# SCH_ZX_WiFi_2022-06-30.net
KiCad netlist of a schematic drawn in EasyEDA
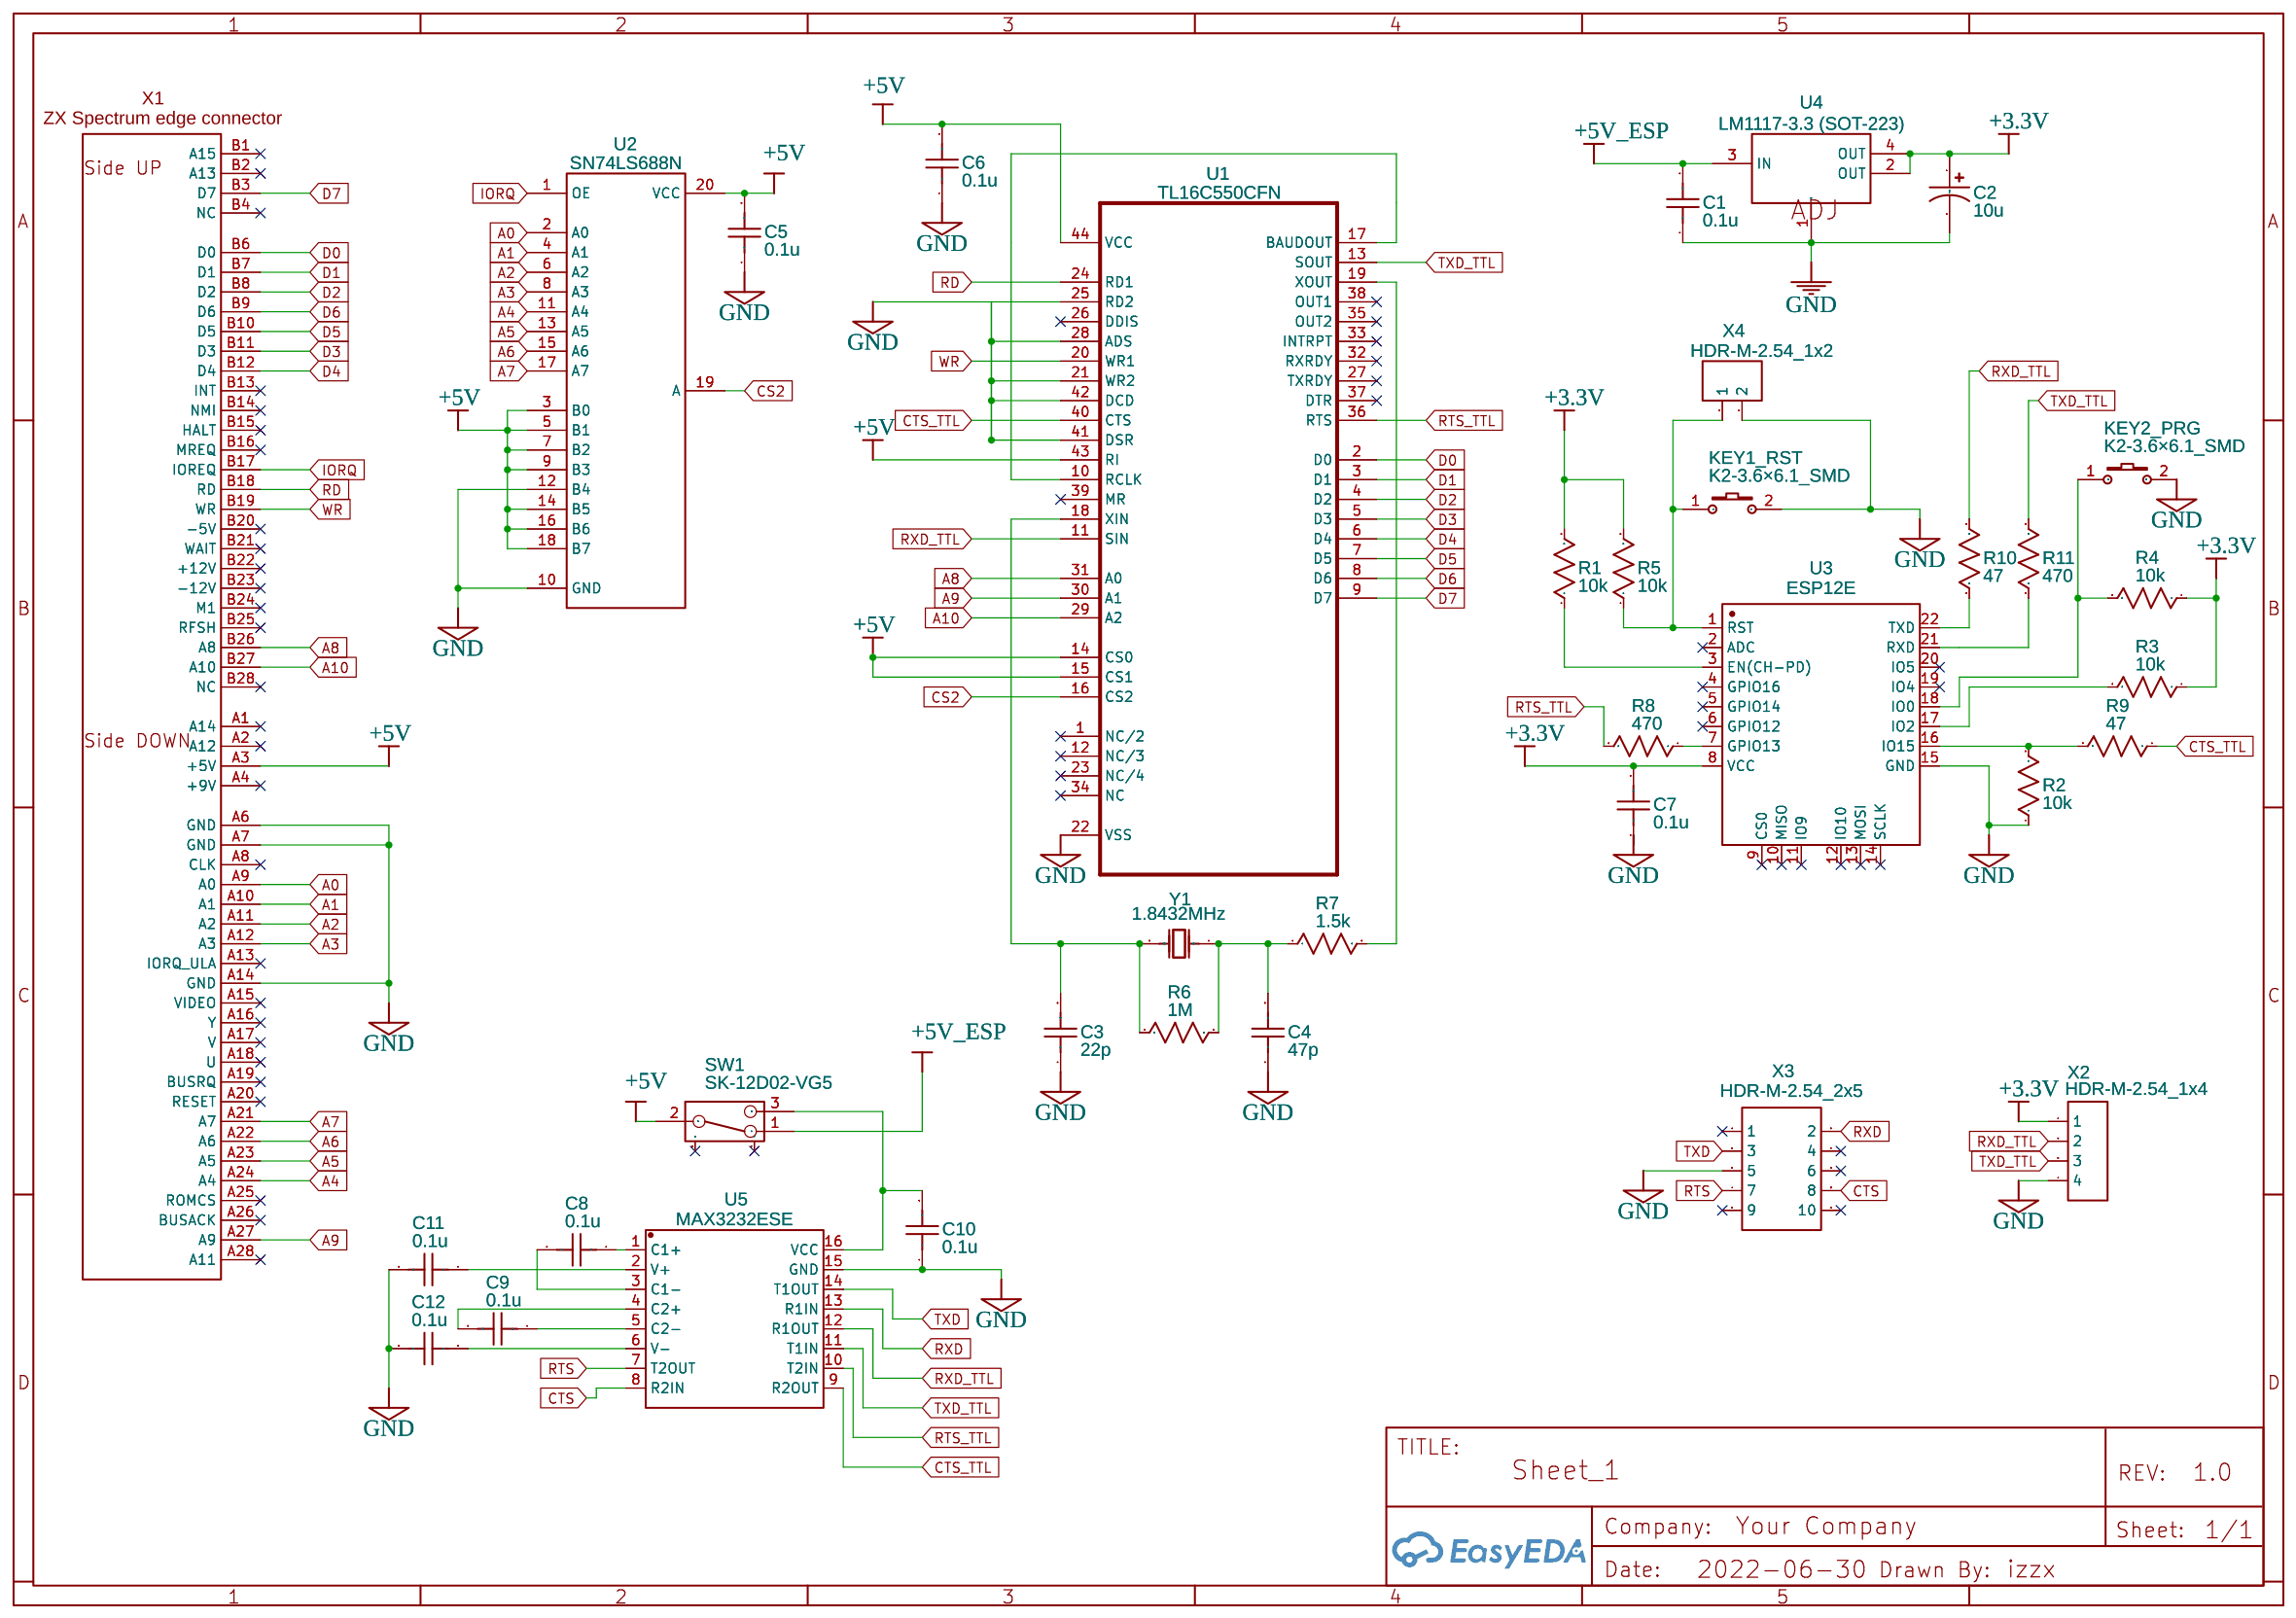
[diagram p0: schematic sheet]

(export (version "E")
  (design (tool "Eeschema 10.0.6"))
  (components
    (comp (ref "C1") (value "0.1u") (libsource (lib "") (part "C_0805_US")))
    (comp (ref "C2") (value "10u") (libsource (lib "") (part "C_Tan_SMD_A_US")))
    (comp (ref "C3") (value "22p") (libsource (lib "") (part "C_0805_US")))
    (comp (ref "C4") (value "47p") (libsource (lib "") (part "C_0805_US")))
    (comp (ref "C5") (value "0.1u") (libsource (lib "") (part "C_0805_US")))
    (comp (ref "C6") (value "0.1u") (libsource (lib "") (part "C_0805_US")))
    (comp (ref "C7") (value "0.1u") (libsource (lib "") (part "C_0805_US")))
    (comp (ref "C8") (value "0.1u") (libsource (lib "") (part "C_0805_US_1")))
    (comp (ref "C9") (value "0.1u") (libsource (lib "") (part "C_0805_US_1")))
    (comp (ref "C10") (value "0.1u") (libsource (lib "") (part "C_0805_US")))
    (comp (ref "C11") (value "0.1u") (libsource (lib "") (part "C_0805_US_1")))
    (comp (ref "C12") (value "0.1u") (libsource (lib "") (part "C_0805_US_1")))
    (comp (ref "KEY1_RST")
      (value "K2-3.6×6.1_SMD")
      (fields
        (field (name "BOM_Manufacturer Part") "K2-1107ST-A4SW-06")
        (field (name "BOM_Supplier Part") "C118141")
      )
      (libsource (lib "") (part "K2-3.6×6.1_SMD"))
    )
    (comp (ref "KEY2_PRG")
      (value "K2-3.6×6.1_SMD")
      (fields
        (field (name "BOM_Manufacturer Part") "K2-1107ST-A4SW-06")
        (field (name "BOM_Supplier Part") "C118141")
      )
      (libsource (lib "") (part "K2-3.6×6.1_SMD_1"))
    )
    (comp (ref "R1") (value "10k") (libsource (lib "") (part "R_0805_US")))
    (comp (ref "R2") (value "10k") (libsource (lib "") (part "R_0805_US")))
    (comp (ref "R3") (value "10k") (libsource (lib "") (part "R_0805_US_1")))
    (comp (ref "R4") (value "10k") (libsource (lib "") (part "R_0805_US_1")))
    (comp (ref "R5") (value "10k") (libsource (lib "") (part "R_0805_US")))
    (comp (ref "R6") (value "1M") (libsource (lib "") (part "R_0805_US_2")))
    (comp (ref "R7") (value "1.5k") (libsource (lib "") (part "R_0805_US_2")))
    (comp (ref "R8") (value "470") (libsource (lib "") (part "R_0805_US_1")))
    (comp (ref "R9") (value "47") (libsource (lib "") (part "R_0805_US_1")))
    (comp (ref "R10") (value "47") (libsource (lib "") (part "R_0805_US")))
    (comp (ref "R11") (value "470") (libsource (lib "") (part "R_0805_US")))
    (comp (ref "SW1")
      (value "SK-12D02-VG5")
      (fields (field (name "BOM_Supplier Part") "C136722"))
      (libsource (lib "") (part "SK-12D02-VG5"))
    )
    (comp (ref "U1") (value "TL16C550CFN") (libsource (lib "") (part "TL16C550CFN")))
    (comp (ref "U2") (value "SN74LS688N") (libsource (lib "") (part "SN74LS688N")))
    (comp (ref "U3") (value "ESP12E") (libsource (lib "") (part "ESP12E/F")))
    (comp (ref "U4")
      (value "LM1117-3.3 (SOT-223)")
      (fields
        (field (name "BOM_Manufacturer Part") "LM317G-AA3-R")
        (field (name "BOM_Supplier Part") "C19651")
      )
      (libsource (lib "") (part "LM317(SOT-223)"))
    )
    (comp (ref "U5")
      (value "MAX3232ESE")
      (fields (field (name "BOM_Supplier Part") "C2904738"))
      (libsource (lib "") (part "MAX3232ESE"))
    )
    (comp (ref "X1") (value "ZX SPECTRUM CONNECTOR") (libsource (lib "") (part "ZX SPECTRUM CONNECTOR")))
    (comp (ref "X2")
      (value "HDR-M-2.54_1x4")
      (fields (field (name "BOM_Supplier Part") "C124378"))
      (libsource (lib "") (part "HDR-M-2.54_1x4"))
    )
    (comp (ref "X3")
      (value "HDR-M-2.54_2x5")
      (fields (field (name "BOM_Supplier Part") "C178292"))
      (libsource (lib "") (part "HDR-M-2.54_2x5"))
    )
    (comp (ref "X4")
      (value "HDR-M-2.54_1x2")
      (fields (field (name "BOM_Supplier Part") "C124375"))
      (libsource (lib "") (part "HDR-M-2.54_1x2"))
    )
    (comp (ref "Y1")
      (value "1.8432MHz")
      (fields
        (field (name "BOM_Manufacturer Part") "X49UD3579MSD2SC")
        (field (name "BOM_Supplier Part") "C36564")
      )
      (libsource (lib "") (part "X49UD3579MSD2SC"))
    )
  )
  (nets
    (net (code "1") (name "+3.3V") (class "Default")
      (node (ref "C2") (pin "1") (pinfunction "1_1") (pintype "unspecified"))
      (node (ref "C7") (pin "2") (pinfunction "2_2") (pintype "unspecified"))
      (node (ref "R1") (pin "2") (pinfunction "2_2") (pintype "unspecified"))
      (node (ref "R3") (pin "1") (pinfunction "1_1") (pintype "unspecified"))
      (node (ref "R4") (pin "1") (pinfunction "1_1") (pintype "unspecified"))
      (node (ref "R5") (pin "2") (pinfunction "2_2") (pintype "unspecified"))
      (node (ref "U3") (pin "8") (pinfunction "VCC_8") (pintype "unspecified"))
      (node (ref "U4") (pin "2") (pinfunction "OUT_2") (pintype "passive"))
      (node (ref "U4") (pin "4") (pinfunction "OUT_4") (pintype "passive"))
      (node (ref "X2") (pin "1") (pinfunction "1_1") (pintype "unspecified"))
    )
    (net (code "2") (name "+5V") (class "Default")
      (node (ref "C5") (pin "2") (pinfunction "2_2") (pintype "unspecified"))
      (node (ref "C6") (pin "2") (pinfunction "2_2") (pintype "unspecified"))
      (node (ref "SW1") (pin "2") (pinfunction "2_2") (pintype "unspecified"))
      (node (ref "U1") (pin "14") (pinfunction "CS0_14") (pintype "input"))
      (node (ref "U1") (pin "15") (pinfunction "CS1_15") (pintype "input"))
      (node (ref "U1") (pin "43") (pinfunction "RI_43") (pintype "input"))
      (node (ref "U1") (pin "44") (pinfunction "VCC_44") (pintype "passive"))
      (node (ref "U2") (pin "14") (pinfunction "B5_14") (pintype "unspecified"))
      (node (ref "U2") (pin "16") (pinfunction "B6_16") (pintype "unspecified"))
      (node (ref "U2") (pin "18") (pinfunction "B7_18") (pintype "unspecified"))
      (node (ref "U2") (pin "20") (pinfunction "VCC_20") (pintype "passive"))
      (node (ref "U2") (pin "3") (pinfunction "B0_3") (pintype "unspecified"))
      (node (ref "U2") (pin "5") (pinfunction "B1_5") (pintype "unspecified"))
      (node (ref "U2") (pin "7") (pinfunction "B2_7") (pintype "unspecified"))
      (node (ref "U2") (pin "9") (pinfunction "B3_9") (pintype "unspecified"))
      (node (ref "X1") (pin "A3") (pinfunction "+5V_A3") (pintype "unspecified"))
    )
    (net (code "3") (name "+5V_ESP") (class "Default")
      (node (ref "C1") (pin "2") (pinfunction "2_2") (pintype "unspecified"))
      (node (ref "SW1") (pin "1") (pinfunction "1_1") (pintype "unspecified"))
      (node (ref "U4") (pin "3") (pinfunction "IN_3") (pintype "passive"))
    )
    (net (code "4") (name "A0") (class "Default")
      (node (ref "U2") (pin "2") (pinfunction "A0_2") (pintype "unspecified"))
      (node (ref "X1") (pin "A9") (pinfunction "A0_A9") (pintype "unspecified"))
    )
    (net (code "5") (name "A1") (class "Default")
      (node (ref "U2") (pin "4") (pinfunction "A1_4") (pintype "unspecified"))
      (node (ref "X1") (pin "A10") (pinfunction "A1_A10") (pintype "unspecified"))
    )
    (net (code "6") (name "A2") (class "Default")
      (node (ref "U2") (pin "6") (pinfunction "A2_6") (pintype "unspecified"))
      (node (ref "X1") (pin "A11") (pinfunction "A2_A11") (pintype "unspecified"))
    )
    (net (code "7") (name "A3") (class "Default")
      (node (ref "U2") (pin "8") (pinfunction "A3_8") (pintype "unspecified"))
      (node (ref "X1") (pin "A12") (pinfunction "A3_A12") (pintype "unspecified"))
    )
    (net (code "8") (name "A4") (class "Default")
      (node (ref "U2") (pin "11") (pinfunction "A4_11") (pintype "unspecified"))
      (node (ref "X1") (pin "A24") (pinfunction "A4_A24") (pintype "unspecified"))
    )
    (net (code "9") (name "A5") (class "Default")
      (node (ref "U2") (pin "13") (pinfunction "A5_13") (pintype "unspecified"))
      (node (ref "X1") (pin "A23") (pinfunction "A5_A23") (pintype "unspecified"))
    )
    (net (code "10") (name "A6") (class "Default")
      (node (ref "U2") (pin "15") (pinfunction "A6_15") (pintype "unspecified"))
      (node (ref "X1") (pin "A22") (pinfunction "A6_A22") (pintype "unspecified"))
    )
    (net (code "11") (name "A7") (class "Default")
      (node (ref "U2") (pin "17") (pinfunction "A7_17") (pintype "unspecified"))
      (node (ref "X1") (pin "A21") (pinfunction "A7_A21") (pintype "unspecified"))
    )
    (net (code "12") (name "A8") (class "Default")
      (node (ref "U1") (pin "31") (pinfunction "A0_31") (pintype "input"))
      (node (ref "X1") (pin "B26") (pinfunction "A8_B26") (pintype "unspecified"))
    )
    (net (code "13") (name "A9") (class "Default")
      (node (ref "U1") (pin "30") (pinfunction "A1_30") (pintype "input"))
      (node (ref "X1") (pin "A27") (pinfunction "A9_A27") (pintype "unspecified"))
    )
    (net (code "14") (name "A10") (class "Default")
      (node (ref "U1") (pin "29") (pinfunction "A2_29") (pintype "input"))
      (node (ref "X1") (pin "B27") (pinfunction "A10_B27") (pintype "unspecified"))
    )
    (net (code "15") (name "CS2") (class "Default")
      (node (ref "U1") (pin "16") (pinfunction "CS2_16") (pintype "input"))
      (node (ref "U2") (pin "19") (pinfunction "A_19") (pintype "output"))
    )
    (net (code "16") (name "CTS") (class "Default")
      (node (ref "U5") (pin "8") (pinfunction "R2IN_8") (pintype "unspecified"))
      (node (ref "X3") (pin "8") (pinfunction "8_8") (pintype "unspecified"))
    )
    (net (code "17") (name "CTS_TTL") (class "Default")
      (node (ref "R9") (pin "1") (pinfunction "1_1") (pintype "unspecified"))
      (node (ref "U1") (pin "40") (pinfunction "CTS_40") (pintype "input"))
      (node (ref "U5") (pin "9") (pinfunction "R2OUT_9") (pintype "unspecified"))
    )
    (net (code "18") (name "D0") (class "Default")
      (node (ref "U1") (pin "2") (pinfunction "D0_2") (pintype "unspecified"))
      (node (ref "X1") (pin "B6") (pinfunction "D0_B6") (pintype "bidirectional"))
    )
    (net (code "19") (name "D1") (class "Default")
      (node (ref "U1") (pin "3") (pinfunction "D1_3") (pintype "unspecified"))
      (node (ref "X1") (pin "B7") (pinfunction "D1_B7") (pintype "bidirectional"))
    )
    (net (code "20") (name "D2") (class "Default")
      (node (ref "U1") (pin "4") (pinfunction "D2_4") (pintype "unspecified"))
      (node (ref "X1") (pin "B8") (pinfunction "D2_B8") (pintype "bidirectional"))
    )
    (net (code "21") (name "D3") (class "Default")
      (node (ref "U1") (pin "5") (pinfunction "D3_5") (pintype "unspecified"))
      (node (ref "X1") (pin "B11") (pinfunction "D3_B11") (pintype "unspecified"))
    )
    (net (code "22") (name "D4") (class "Default")
      (node (ref "U1") (pin "6") (pinfunction "D4_6") (pintype "unspecified"))
      (node (ref "X1") (pin "B12") (pinfunction "D4_B12") (pintype "unspecified"))
    )
    (net (code "23") (name "D5") (class "Default")
      (node (ref "U1") (pin "7") (pinfunction "D5_7") (pintype "unspecified"))
      (node (ref "X1") (pin "B10") (pinfunction "D5_B10") (pintype "bidirectional"))
    )
    (net (code "24") (name "D6") (class "Default")
      (node (ref "U1") (pin "8") (pinfunction "D6_8") (pintype "unspecified"))
      (node (ref "X1") (pin "B9") (pinfunction "D6_B9") (pintype "unspecified"))
    )
    (net (code "25") (name "D7") (class "Default")
      (node (ref "U1") (pin "9") (pinfunction "D7_9") (pintype "unspecified"))
      (node (ref "X1") (pin "B3") (pinfunction "D7_B3") (pintype "bidirectional"))
    )
    (net (code "26") (name "GND") (class "Default")
      (node (ref "C1") (pin "1") (pinfunction "1_1") (pintype "unspecified"))
      (node (ref "C10") (pin "1") (pinfunction "1_1") (pintype "unspecified"))
      (node (ref "C11") (pin "2") (pinfunction "2_2") (pintype "unspecified"))
      (node (ref "C12") (pin "2") (pinfunction "2_2") (pintype "unspecified"))
      (node (ref "C2") (pin "2") (pinfunction "2_2") (pintype "unspecified"))
      (node (ref "C3") (pin "1") (pinfunction "1_1") (pintype "unspecified"))
      (node (ref "C4") (pin "1") (pinfunction "1_1") (pintype "unspecified"))
      (node (ref "C5") (pin "1") (pinfunction "1_1") (pintype "unspecified"))
      (node (ref "C6") (pin "1") (pinfunction "1_1") (pintype "unspecified"))
      (node (ref "C7") (pin "1") (pinfunction "1_1") (pintype "unspecified"))
      (node (ref "KEY1_RST") (pin "2") (pinfunction "2_2") (pintype "unspecified"))
      (node (ref "KEY2_PRG") (pin "2") (pinfunction "2_2") (pintype "unspecified"))
      (node (ref "R2") (pin "1") (pinfunction "1_1") (pintype "unspecified"))
      (node (ref "U1") (pin "21") (pinfunction "WR2_21") (pintype "input"))
      (node (ref "U1") (pin "22") (pinfunction "VSS_22") (pintype "passive"))
      (node (ref "U1") (pin "25") (pinfunction "RD2_25") (pintype "input"))
      (node (ref "U1") (pin "28") (pinfunction "ADS_28") (pintype "input"))
      (node (ref "U1") (pin "41") (pinfunction "DSR_41") (pintype "input"))
      (node (ref "U1") (pin "42") (pinfunction "DCD_42") (pintype "input"))
      (node (ref "U2") (pin "10") (pinfunction "GND_10") (pintype "passive"))
      (node (ref "U2") (pin "12") (pinfunction "B4_12") (pintype "unspecified"))
      (node (ref "U3") (pin "15") (pinfunction "GND_15") (pintype "unspecified"))
      (node (ref "U4") (pin "1") (pinfunction "ADJ_1") (pintype "passive"))
      (node (ref "U5") (pin "15") (pinfunction "GND_15") (pintype "unspecified"))
      (node (ref "X1") (pin "A14") (pinfunction "GND_A14") (pintype "unspecified"))
      (node (ref "X1") (pin "A6") (pinfunction "GND_A6") (pintype "unspecified"))
      (node (ref "X1") (pin "A7") (pinfunction "GND_A7") (pintype "unspecified"))
      (node (ref "X2") (pin "4") (pinfunction "4_4") (pintype "unspecified"))
      (node (ref "X3") (pin "5") (pinfunction "5_5") (pintype "unspecified"))
      (node (ref "X4") (pin "2") (pinfunction "2_2") (pintype "unspecified"))
    )
    (net (code "27") (name "IORQ") (class "Default")
      (node (ref "U2") (pin "1") (pinfunction "OE_1") (pintype "unspecified"))
      (node (ref "X1") (pin "B17") (pinfunction "IOREQ_B17") (pintype "unspecified"))
    )
    (net (code "28") (name "Net-(U1-BAUDOUT)") (class "Default")
      (node (ref "U1") (pin "10") (pinfunction "RCLK_10") (pintype "input"))
      (node (ref "U1") (pin "17") (pinfunction "BAUDOUT_17") (pintype "output"))
    )
    (net (code "29") (name "Net-(U1-XIN)") (class "Default")
      (node (ref "C3") (pin "2") (pinfunction "2_2") (pintype "unspecified"))
      (node (ref "R6") (pin "1") (pinfunction "1_1") (pintype "unspecified"))
      (node (ref "U1") (pin "18") (pinfunction "XIN_18") (pintype "input"))
      (node (ref "Y1") (pin "2") (pinfunction "OSC2_2") (pintype "input"))
    )
    (net (code "30") (name "Net-(U1-XOUT)") (class "Default")
      (node (ref "R7") (pin "2") (pinfunction "2_2") (pintype "unspecified"))
      (node (ref "U1") (pin "19") (pinfunction "XOUT_19") (pintype "output"))
    )
    (net (code "31") (name "Net-(U3-EN(CH-PD))") (class "Default")
      (node (ref "R1") (pin "1") (pinfunction "1_1") (pintype "unspecified"))
      (node (ref "U3") (pin "3") (pinfunction "EN(CH-PD)_3") (pintype "unspecified"))
    )
    (net (code "32") (name "Net-(U3-GPIO13)") (class "Default")
      (node (ref "R8") (pin "1") (pinfunction "1_1") (pintype "unspecified"))
      (node (ref "U3") (pin "7") (pinfunction "GPIO13_7") (pintype "unspecified"))
    )
    (net (code "33") (name "Net-(U3-IO0)") (class "Default")
      (node (ref "KEY2_PRG") (pin "1") (pinfunction "1_1") (pintype "unspecified"))
      (node (ref "R4") (pin "2") (pinfunction "2_2") (pintype "unspecified"))
      (node (ref "U3") (pin "18") (pinfunction "IO0_18") (pintype "unspecified"))
    )
    (net (code "34") (name "Net-(U3-IO2)") (class "Default")
      (node (ref "R3") (pin "2") (pinfunction "2_2") (pintype "unspecified"))
      (node (ref "U3") (pin "17") (pinfunction "IO2_17") (pintype "unspecified"))
    )
    (net (code "35") (name "Net-(U3-IO15)") (class "Default")
      (node (ref "R2") (pin "2") (pinfunction "2_2") (pintype "unspecified"))
      (node (ref "R9") (pin "2") (pinfunction "2_2") (pintype "unspecified"))
      (node (ref "U3") (pin "16") (pinfunction "IO15_16") (pintype "unspecified"))
    )
    (net (code "36") (name "Net-(U3-RST)") (class "Default")
      (node (ref "KEY1_RST") (pin "1") (pinfunction "1_1") (pintype "unspecified"))
      (node (ref "R5") (pin "1") (pinfunction "1_1") (pintype "unspecified"))
      (node (ref "U3") (pin "1") (pinfunction "RST_1") (pintype "unspecified"))
      (node (ref "X4") (pin "1") (pinfunction "1_1") (pintype "unspecified"))
    )
    (net (code "37") (name "Net-(U3-RXD)") (class "Default")
      (node (ref "R11") (pin "1") (pinfunction "1_1") (pintype "unspecified"))
      (node (ref "U3") (pin "21") (pinfunction "RXD_21") (pintype "unspecified"))
    )
    (net (code "38") (name "Net-(U3-TXD)") (class "Default")
      (node (ref "R10") (pin "1") (pinfunction "1_1") (pintype "unspecified"))
      (node (ref "U3") (pin "22") (pinfunction "TXD_22") (pintype "unspecified"))
    )
    (net (code "39") (name "Net-(U5-C1+)") (class "Default")
      (node (ref "C8") (pin "1") (pinfunction "1_1") (pintype "unspecified"))
      (node (ref "U5") (pin "1") (pinfunction "C1+_1") (pintype "unspecified"))
    )
    (net (code "40") (name "Net-(U5-C1-)") (class "Default")
      (node (ref "C8") (pin "2") (pinfunction "2_2") (pintype "unspecified"))
      (node (ref "U5") (pin "3") (pinfunction "C1-_3") (pintype "unspecified"))
    )
    (net (code "41") (name "Net-(U5-C2+)") (class "Default")
      (node (ref "C9") (pin "2") (pinfunction "2_2") (pintype "unspecified"))
      (node (ref "U5") (pin "4") (pinfunction "C2+_4") (pintype "unspecified"))
    )
    (net (code "42") (name "Net-(U5-C2-)") (class "Default")
      (node (ref "C9") (pin "1") (pinfunction "1_1") (pintype "unspecified"))
      (node (ref "U5") (pin "5") (pinfunction "C2-_5") (pintype "unspecified"))
    )
    (net (code "43") (name "Net-(U5-V+)") (class "Default")
      (node (ref "C11") (pin "1") (pinfunction "1_1") (pintype "unspecified"))
      (node (ref "U5") (pin "2") (pinfunction "V+_2") (pintype "unspecified"))
    )
    (net (code "44") (name "Net-(U5-V-)") (class "Default")
      (node (ref "C12") (pin "1") (pinfunction "1_1") (pintype "unspecified"))
      (node (ref "U5") (pin "6") (pinfunction "V-_6") (pintype "unspecified"))
    )
    (net (code "45") (name "Net-(U5-VCC)") (class "Default")
      (node (ref "C10") (pin "2") (pinfunction "2_2") (pintype "unspecified"))
      (node (ref "SW1") (pin "3") (pinfunction "3_3") (pintype "unspecified"))
      (node (ref "U5") (pin "16") (pinfunction "VCC_16") (pintype "unspecified"))
    )
    (net (code "46") (name "Net-(Y1-OSC1)") (class "Default")
      (node (ref "C4") (pin "2") (pinfunction "2_2") (pintype "unspecified"))
      (node (ref "R6") (pin "2") (pinfunction "2_2") (pintype "unspecified"))
      (node (ref "R7") (pin "1") (pinfunction "1_1") (pintype "unspecified"))
      (node (ref "Y1") (pin "1") (pinfunction "OSC1_1") (pintype "input"))
    )
    (net (code "47") (name "RD") (class "Default")
      (node (ref "U1") (pin "24") (pinfunction "RD1_24") (pintype "input"))
      (node (ref "X1") (pin "B18") (pinfunction "RD_B18") (pintype "unspecified"))
    )
    (net (code "48") (name "RTS") (class "Default")
      (node (ref "U5") (pin "7") (pinfunction "T2OUT_7") (pintype "unspecified"))
      (node (ref "X3") (pin "7") (pinfunction "7_7") (pintype "unspecified"))
    )
    (net (code "49") (name "RTS_TTL") (class "Default")
      (node (ref "R8") (pin "2") (pinfunction "2_2") (pintype "unspecified"))
      (node (ref "U1") (pin "36") (pinfunction "RTS_36") (pintype "output"))
      (node (ref "U5") (pin "10") (pinfunction "T2IN_10") (pintype "unspecified"))
    )
    (net (code "50") (name "RXD") (class "Default")
      (node (ref "U5") (pin "13") (pinfunction "R1IN_13") (pintype "unspecified"))
      (node (ref "X3") (pin "2") (pinfunction "2_2") (pintype "unspecified"))
    )
    (net (code "51") (name "RXD_TTL") (class "Default")
      (node (ref "R10") (pin "2") (pinfunction "2_2") (pintype "unspecified"))
      (node (ref "U1") (pin "11") (pinfunction "SIN_11") (pintype "input"))
      (node (ref "U5") (pin "12") (pinfunction "R1OUT_12") (pintype "unspecified"))
      (node (ref "X2") (pin "2") (pinfunction "2_2") (pintype "unspecified"))
    )
    (net (code "52") (name "TXD") (class "Default")
      (node (ref "U5") (pin "14") (pinfunction "T1OUT_14") (pintype "unspecified"))
      (node (ref "X3") (pin "3") (pinfunction "3_3") (pintype "unspecified"))
    )
    (net (code "53") (name "TXD_TTL") (class "Default")
      (node (ref "R11") (pin "2") (pinfunction "2_2") (pintype "unspecified"))
      (node (ref "U1") (pin "13") (pinfunction "SOUT_13") (pintype "output"))
      (node (ref "U5") (pin "11") (pinfunction "T1IN_11") (pintype "unspecified"))
      (node (ref "X2") (pin "3") (pinfunction "3_3") (pintype "unspecified"))
    )
    (net (code "54") (name "WR") (class "Default")
      (node (ref "U1") (pin "20") (pinfunction "WR1_20") (pintype "input"))
      (node (ref "X1") (pin "B19") (pinfunction "WR_B19") (pintype "unspecified"))
    )
    (net (code "55") (name "unconnected-(SW1-Pad4)") (class "Default")
      (node (ref "SW1") (pin "4") (pinfunction "4_4") (pintype "unspecified+no_connect"))
    )
    (net (code "56") (name "unconnected-(SW1-Pad5)") (class "Default")
      (node (ref "SW1") (pin "5") (pinfunction "5_5") (pintype "unspecified+no_connect"))
    )
    (net (code "57") (name "unconnected-(U1-DDIS-Pad26)") (class "Default")
      (node (ref "U1") (pin "26") (pinfunction "DDIS_26") (pintype "input+no_connect"))
    )
    (net (code "58") (name "unconnected-(U1-DTR-Pad37)") (class "Default")
      (node (ref "U1") (pin "37") (pinfunction "DTR_37") (pintype "output+no_connect"))
    )
    (net (code "59") (name "unconnected-(U1-INTRPT-Pad33)") (class "Default")
      (node (ref "U1") (pin "33") (pinfunction "INTRPT_33") (pintype "output+no_connect"))
    )
    (net (code "60") (name "unconnected-(U1-MR-Pad39)") (class "Default")
      (node (ref "U1") (pin "39") (pinfunction "MR_39") (pintype "input+no_connect"))
    )
    (net (code "61") (name "unconnected-(U1-NC-Pad34)") (class "Default")
      (node (ref "U1") (pin "34") (pinfunction "NC_34") (pintype "unspecified+no_connect"))
    )
    (net (code "62") (name "unconnected-(U1-NC{slash}2-Pad1)") (class "Default")
      (node (ref "U1") (pin "1") (pinfunction "NC/2_1") (pintype "unspecified+no_connect"))
    )
    (net (code "63") (name "unconnected-(U1-NC{slash}3-Pad12)") (class "Default")
      (node (ref "U1") (pin "12") (pinfunction "NC/3_12") (pintype "unspecified+no_connect"))
    )
    (net (code "64") (name "unconnected-(U1-NC{slash}4-Pad23)") (class "Default")
      (node (ref "U1") (pin "23") (pinfunction "NC/4_23") (pintype "unspecified+no_connect"))
    )
    (net (code "65") (name "unconnected-(U1-OUT1-Pad38)") (class "Default")
      (node (ref "U1") (pin "38") (pinfunction "OUT1_38") (pintype "output+no_connect"))
    )
    (net (code "66") (name "unconnected-(U1-OUT2-Pad35)") (class "Default")
      (node (ref "U1") (pin "35") (pinfunction "OUT2_35") (pintype "output+no_connect"))
    )
    (net (code "67") (name "unconnected-(U1-RXRDY-Pad32)") (class "Default")
      (node (ref "U1") (pin "32") (pinfunction "RXRDY_32") (pintype "output+no_connect"))
    )
    (net (code "68") (name "unconnected-(U1-TXRDY-Pad27)") (class "Default")
      (node (ref "U1") (pin "27") (pinfunction "TXRDY_27") (pintype "output+no_connect"))
    )
    (net (code "69") (name "unconnected-(U3-ADC-Pad2)") (class "Default")
      (node (ref "U3") (pin "2") (pinfunction "ADC_2") (pintype "unspecified+no_connect"))
    )
    (net (code "70") (name "unconnected-(U3-CS0-Pad9)") (class "Default")
      (node (ref "U3") (pin "9") (pinfunction "CS0_9") (pintype "unspecified+no_connect"))
    )
    (net (code "71") (name "unconnected-(U3-GPIO12-Pad6)") (class "Default")
      (node (ref "U3") (pin "6") (pinfunction "GPIO12_6") (pintype "unspecified+no_connect"))
    )
    (net (code "72") (name "unconnected-(U3-GPIO14-Pad5)") (class "Default")
      (node (ref "U3") (pin "5") (pinfunction "GPIO14_5") (pintype "unspecified+no_connect"))
    )
    (net (code "73") (name "unconnected-(U3-GPIO16-Pad4)") (class "Default")
      (node (ref "U3") (pin "4") (pinfunction "GPIO16_4") (pintype "unspecified+no_connect"))
    )
    (net (code "74") (name "unconnected-(U3-IO4-Pad19)") (class "Default")
      (node (ref "U3") (pin "19") (pinfunction "IO4_19") (pintype "unspecified+no_connect"))
    )
    (net (code "75") (name "unconnected-(U3-IO5-Pad20)") (class "Default")
      (node (ref "U3") (pin "20") (pinfunction "IO5_20") (pintype "unspecified+no_connect"))
    )
    (net (code "76") (name "unconnected-(U3-IO9-Pad11)") (class "Default")
      (node (ref "U3") (pin "11") (pinfunction "IO9_11") (pintype "unspecified+no_connect"))
    )
    (net (code "77") (name "unconnected-(U3-IO10-Pad12)") (class "Default")
      (node (ref "U3") (pin "12") (pinfunction "IO10_12") (pintype "unspecified+no_connect"))
    )
    (net (code "78") (name "unconnected-(U3-MISO-Pad10)") (class "Default")
      (node (ref "U3") (pin "10") (pinfunction "MISO_10") (pintype "unspecified+no_connect"))
    )
    (net (code "79") (name "unconnected-(U3-MOSI-Pad13)") (class "Default")
      (node (ref "U3") (pin "13") (pinfunction "MOSI_13") (pintype "unspecified+no_connect"))
    )
    (net (code "80") (name "unconnected-(U3-SCLK-Pad14)") (class "Default")
      (node (ref "U3") (pin "14") (pinfunction "SCLK_14") (pintype "unspecified+no_connect"))
    )
    (net (code "81") (name "unconnected-(X1-+9V-PadA4)") (class "Default")
      (node (ref "X1") (pin "A4") (pinfunction "+9V_A4") (pintype "unspecified+no_connect"))
    )
    (net (code "82") (name "unconnected-(X1-+12V-PadB22)") (class "Default")
      (node (ref "X1") (pin "B22") (pinfunction "+12V_B22") (pintype "unspecified+no_connect"))
    )
    (net (code "83") (name "unconnected-(X1--5V-PadB20)") (class "Default")
      (node (ref "X1") (pin "B20") (pinfunction "-5V_B20") (pintype "unspecified+no_connect"))
    )
    (net (code "84") (name "unconnected-(X1--12V-PadB23)") (class "Default")
      (node (ref "X1") (pin "B23") (pinfunction "-12V_B23") (pintype "unspecified+no_connect"))
    )
    (net (code "85") (name "unconnected-(X1-A11-PadA28)") (class "Default")
      (node (ref "X1") (pin "A28") (pinfunction "A11_A28") (pintype "unspecified+no_connect"))
    )
    (net (code "86") (name "unconnected-(X1-A12-PadA2)") (class "Default")
      (node (ref "X1") (pin "A2") (pinfunction "A12_A2") (pintype "unspecified+no_connect"))
    )
    (net (code "87") (name "unconnected-(X1-A13-PadB2)") (class "Default")
      (node (ref "X1") (pin "B2") (pinfunction "A13_B2") (pintype "output+no_connect"))
    )
    (net (code "88") (name "unconnected-(X1-A14-PadA1)") (class "Default")
      (node (ref "X1") (pin "A1") (pinfunction "A14_A1") (pintype "unspecified+no_connect"))
    )
    (net (code "89") (name "unconnected-(X1-A15-PadB1)") (class "Default")
      (node (ref "X1") (pin "B1") (pinfunction "A15_B1") (pintype "output+no_connect"))
    )
    (net (code "90") (name "unconnected-(X1-BUSACK-PadA26)") (class "Default")
      (node (ref "X1") (pin "A26") (pinfunction "BUSACK_A26") (pintype "unspecified+no_connect"))
    )
    (net (code "91") (name "unconnected-(X1-BUSRQ-PadA19)") (class "Default")
      (node (ref "X1") (pin "A19") (pinfunction "BUSRQ_A19") (pintype "unspecified+no_connect"))
    )
    (net (code "92") (name "unconnected-(X1-CLK-PadA8)") (class "Default")
      (node (ref "X1") (pin "A8") (pinfunction "CLK_A8") (pintype "unspecified+no_connect"))
    )
    (net (code "93") (name "unconnected-(X1-HALT-PadB15)") (class "Default")
      (node (ref "X1") (pin "B15") (pinfunction "HALT_B15") (pintype "unspecified+no_connect"))
    )
    (net (code "94") (name "unconnected-(X1-INT-PadB13)") (class "Default")
      (node (ref "X1") (pin "B13") (pinfunction "INT_B13") (pintype "unspecified+no_connect"))
    )
    (net (code "95") (name "unconnected-(X1-IORQ_ULA-PadA13)") (class "Default")
      (node (ref "X1") (pin "A13") (pinfunction "IORQ_ULA_A13") (pintype "unspecified+no_connect"))
    )
    (net (code "96") (name "unconnected-(X1-M1-PadB24)") (class "Default")
      (node (ref "X1") (pin "B24") (pinfunction "M1_B24") (pintype "unspecified+no_connect"))
    )
    (net (code "97") (name "unconnected-(X1-MREQ-PadB16)") (class "Default")
      (node (ref "X1") (pin "B16") (pinfunction "MREQ_B16") (pintype "unspecified+no_connect"))
    )
    (net (code "98") (name "unconnected-(X1-NC-PadB4)") (class "Default")
      (node (ref "X1") (pin "B4") (pinfunction "NC_B4") (pintype "unspecified+no_connect"))
    )
    (net (code "99") (name "unconnected-(X1-NC-PadB28)") (class "Default")
      (node (ref "X1") (pin "B28") (pinfunction "NC_B28") (pintype "unspecified+no_connect"))
    )
    (net (code "100") (name "unconnected-(X1-NMI-PadB14)") (class "Default")
      (node (ref "X1") (pin "B14") (pinfunction "NMI_B14") (pintype "unspecified+no_connect"))
    )
    (net (code "101") (name "unconnected-(X1-RESET-PadA20)") (class "Default")
      (node (ref "X1") (pin "A20") (pinfunction "RESET_A20") (pintype "unspecified+no_connect"))
    )
    (net (code "102") (name "unconnected-(X1-RFSH-PadB25)") (class "Default")
      (node (ref "X1") (pin "B25") (pinfunction "RFSH_B25") (pintype "unspecified+no_connect"))
    )
    (net (code "103") (name "unconnected-(X1-ROMCS-PadA25)") (class "Default")
      (node (ref "X1") (pin "A25") (pinfunction "ROMCS_A25") (pintype "unspecified+no_connect"))
    )
    (net (code "104") (name "unconnected-(X1-U-PadA18)") (class "Default")
      (node (ref "X1") (pin "A18") (pinfunction "U_A18") (pintype "unspecified+no_connect"))
    )
    (net (code "105") (name "unconnected-(X1-V-PadA17)") (class "Default")
      (node (ref "X1") (pin "A17") (pinfunction "V_A17") (pintype "unspecified+no_connect"))
    )
    (net (code "106") (name "unconnected-(X1-VIDEO-PadA15)") (class "Default")
      (node (ref "X1") (pin "A15") (pinfunction "VIDEO_A15") (pintype "unspecified+no_connect"))
    )
    (net (code "107") (name "unconnected-(X1-WAIT-PadB21)") (class "Default")
      (node (ref "X1") (pin "B21") (pinfunction "WAIT_B21") (pintype "unspecified+no_connect"))
    )
    (net (code "108") (name "unconnected-(X1-Y-PadA16)") (class "Default")
      (node (ref "X1") (pin "A16") (pinfunction "Y_A16") (pintype "unspecified+no_connect"))
    )
    (net (code "109") (name "unconnected-(X3-Pad1)") (class "Default")
      (node (ref "X3") (pin "1") (pinfunction "1_1") (pintype "unspecified+no_connect"))
    )
    (net (code "110") (name "unconnected-(X3-Pad4)") (class "Default")
      (node (ref "X3") (pin "4") (pinfunction "4_4") (pintype "unspecified+no_connect"))
    )
    (net (code "111") (name "unconnected-(X3-Pad6)") (class "Default")
      (node (ref "X3") (pin "6") (pinfunction "6_6") (pintype "unspecified+no_connect"))
    )
    (net (code "112") (name "unconnected-(X3-Pad9)") (class "Default")
      (node (ref "X3") (pin "9") (pinfunction "9_9") (pintype "unspecified+no_connect"))
    )
    (net (code "113") (name "unconnected-(X3-Pad10)") (class "Default")
      (node (ref "X3") (pin "10") (pinfunction "10_10") (pintype "unspecified+no_connect"))
    )
  )
)
